# 08_PERIPHERAL.net
KiCad netlist of a schematic drawn in Altium Designer
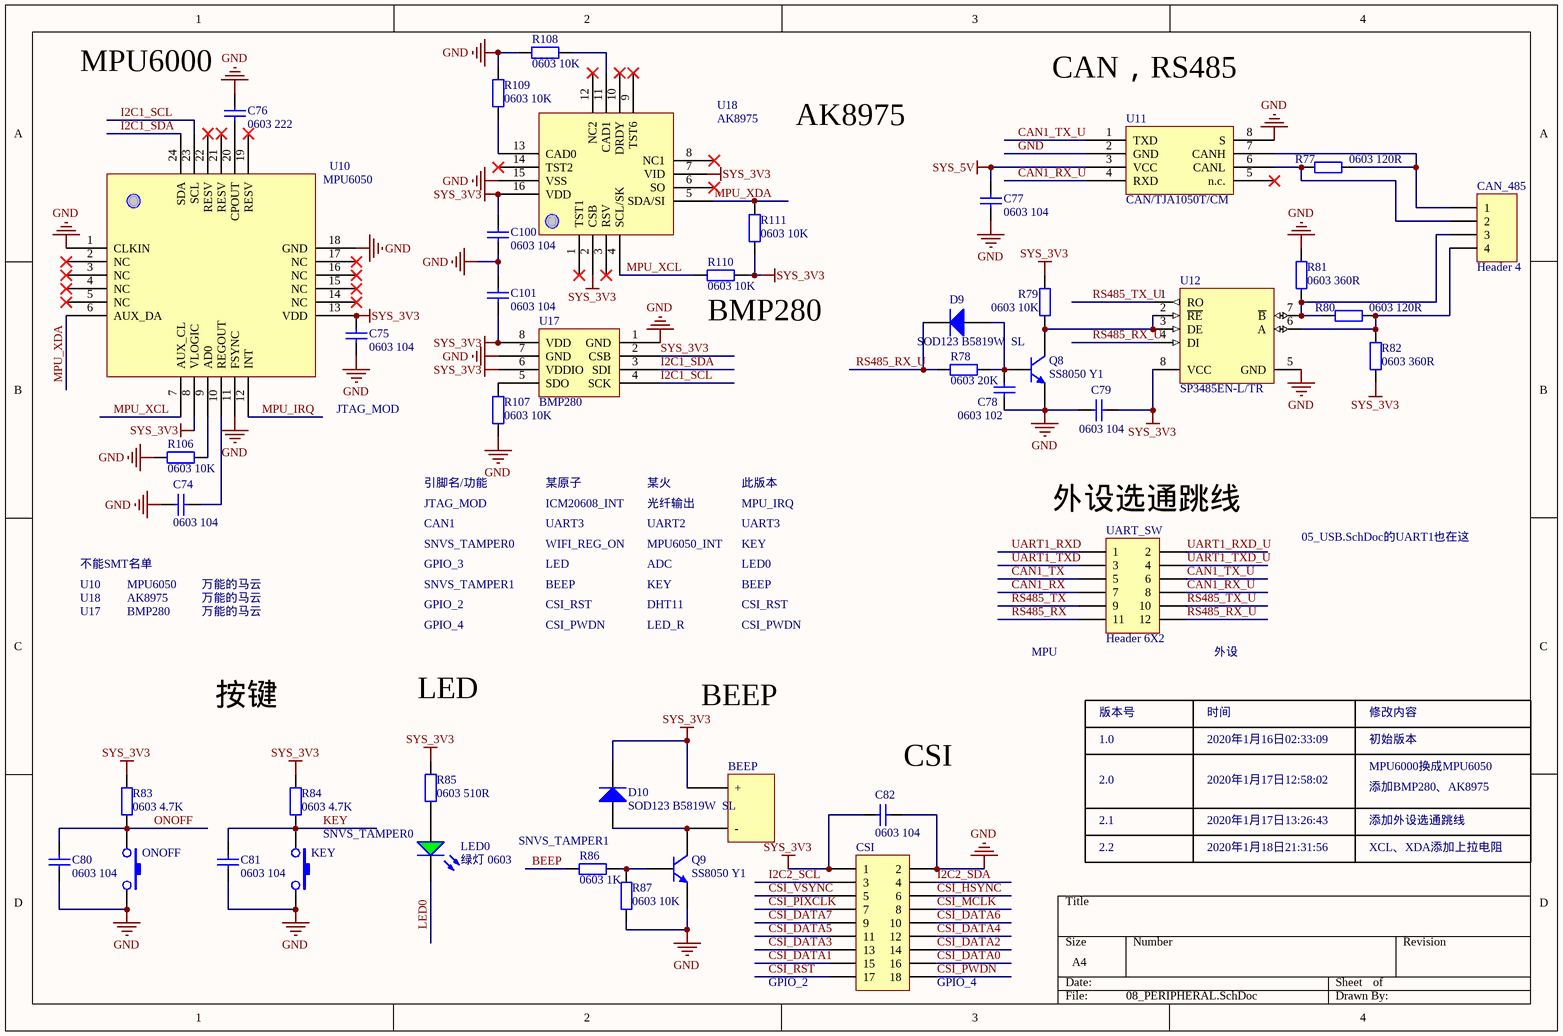
[diagram p0: 08_PERIPHERAL.SchDoc]

(export (version "E")
  (design (tool "Eeschema 10.0.6"))
  (components
    (comp (ref "BEEP") (value "~") (footprint "BEEP") (libsource (lib "Integrated_Library2") (part "BEEP")))
    (comp (ref "C74")
      (value "0603 104")
      (footprint "LC-0603_C")
      (description "贴片电容")
      (libsource (lib "JLC") (part "0603 1.5nF (152) 10% 50V"))
    )
    (comp (ref "C75")
      (value "0603 104")
      (footprint "LC-0603_C")
      (description "贴片电容")
      (libsource (lib "JLC") (part "0603 1.5nF (152) 10% 50V"))
    )
    (comp (ref "C76")
      (value "0603 222")
      (footprint "LC-0603_C")
      (description "贴片电容")
      (libsource (lib "JLC") (part "0603 1.5nF (152) 10% 50V"))
    )
    (comp (ref "C77")
      (value "0603 104")
      (footprint "LC-0603_C")
      (description "贴片电容")
      (libsource (lib "JLC") (part "0603 1.5nF (152) 10% 50V"))
    )
    (comp (ref "C78")
      (value "0603 102")
      (footprint "LC-0603_C")
      (description "贴片电容")
      (libsource (lib "JLC") (part "0603 1.5nF (152) 10% 50V"))
    )
    (comp (ref "C79")
      (value "0603 104")
      (footprint "LC-0603_C")
      (description "贴片电容")
      (libsource (lib "JLC") (part "0603 1.5nF (152) 10% 50V"))
    )
    (comp (ref "C80")
      (value "0603 104")
      (footprint "LC-0603_C")
      (description "贴片电容")
      (libsource (lib "JLC") (part "0603 1.5nF (152) 10% 50V"))
    )
    (comp (ref "C81")
      (value "0603 104")
      (footprint "LC-0603_C")
      (description "贴片电容")
      (libsource (lib "JLC") (part "0603 1.5nF (152) 10% 50V"))
    )
    (comp (ref "C82")
      (value "0603 104")
      (footprint "LC-0603_C")
      (description "贴片电容")
      (libsource (lib "JLC") (part "0603 1.5nF (152) 10% 50V"))
    )
    (comp (ref "C100")
      (value "0603 104")
      (footprint "LC-0603_C")
      (description "贴片电容")
      (libsource (lib "JLC") (part "0603 1.5nF (152) 10% 50V"))
    )
    (comp (ref "C101")
      (value "0603 104")
      (footprint "LC-0603_C")
      (description "贴片电容")
      (libsource (lib "JLC") (part "0603 1.5nF (152) 10% 50V"))
    )
    (comp (ref "CAN_485")
      (value "Header 4")
      (footprint "HDR1X4")
      (description "Header, 4-Pin")
      (fields (field (name "PUBLISHER") "Altium Limited"))
      (libsource (lib "Miscellaneous Connectors") (part "Header 4"))
    )
    (comp (ref "CSI")
      (value "~")
      (footprint "HDR2X9")
      (description "Header, 9-Pin, Dual row")
      (fields (field (name "PUBLISHER") "Altium Limited"))
      (libsource (lib "Miscellaneous Connectors") (part "Header 9X2"))
    )
    (comp (ref "D9")
      (value "SOD123 B5819W  SL")
      (footprint "LC-SOD-123")
      (description "肖特基二极管")
      (libsource (lib "JLC") (part "SOD-123 B5819W  SL"))
    )
    (comp (ref "D10")
      (value "SOD123 B5819W  SL")
      (footprint "LC-SOD-123")
      (description "肖特基二极管")
      (libsource (lib "JLC") (part "SOD-123 B5819W  SL"))
    )
    (comp (ref "KEY") (value "~") (footprint "KEY2") (libsource (lib "Integrated_Library2") (part "KEY")))
    (comp (ref "LED0")
      (value "绿灯 0603")
      (footprint "LC-0603_LED_S1")
      (description "发光二极管")
      (libsource (lib "JLC") (part "0603 绿灯"))
    )
    (comp (ref "ONOFF") (value "~") (footprint "KEY2") (libsource (lib "Integrated_Library2") (part "KEY")))
    (comp (ref "Q8")
      (value "SS8050 Y1")
      (footprint "LC-SOT-23(SOT-23-3)")
      (description "三极管")
      (libsource (lib "JLC") (part "SOT-23 SS8050 Y1"))
    )
    (comp (ref "Q9")
      (value "SS8050 Y1")
      (footprint "LC-SOT-23(SOT-23-3)")
      (description "三极管")
      (libsource (lib "JLC") (part "SOT-23 SS8050 Y1"))
    )
    (comp (ref "R77")
      (value "0603 120R")
      (footprint "LC-0603_R")
      (description "贴片电阻")
      (libsource (lib "") (part "0603 1.1KΩ (1101) 1%_1"))
    )
    (comp (ref "R78")
      (value "0603 20K")
      (footprint "LC-0603_R")
      (description "贴片电阻")
      (libsource (lib "") (part "0603 1.1KΩ (1101) 1%_2"))
    )
    (comp (ref "R79")
      (value "0603 10K")
      (footprint "LC-0603_R")
      (description "贴片电阻")
      (libsource (lib "JLC") (part "0603 1.1KΩ (1101) 1%"))
    )
    (comp (ref "R80")
      (value "0603 120R")
      (footprint "LC-0603_R")
      (description "贴片电阻")
      (libsource (lib "") (part "0603 1.1KΩ (1101) 1%_1"))
    )
    (comp (ref "R81")
      (value "0603 360R")
      (footprint "LC-0603_R")
      (description "贴片电阻")
      (libsource (lib "") (part "0603 1.1KΩ (1101) 1%_3"))
    )
    (comp (ref "R82")
      (value "0603 360R")
      (footprint "LC-0603_R")
      (description "贴片电阻")
      (libsource (lib "") (part "0603 1.1KΩ (1101) 1%_3"))
    )
    (comp (ref "R83")
      (value "0603 4.7K")
      (footprint "LC-0603_R")
      (description "贴片电阻")
      (libsource (lib "") (part "0603 1.1KΩ (1101) 1%_3"))
    )
    (comp (ref "R84")
      (value "0603 4.7K")
      (footprint "LC-0603_R")
      (description "贴片电阻")
      (libsource (lib "") (part "0603 1.1KΩ (1101) 1%_3"))
    )
    (comp (ref "R85")
      (value "0603 510R")
      (footprint "LC-0603_R")
      (description "贴片电阻")
      (libsource (lib "") (part "0603 1.1KΩ (1101) 1%_3"))
    )
    (comp (ref "R86")
      (value "0603 1K")
      (footprint "LC-0603_R")
      (description "贴片电阻")
      (libsource (lib "") (part "0603 1.1KΩ (1101) 1%_2"))
    )
    (comp (ref "R87")
      (value "0603 10K")
      (footprint "LC-0603_R")
      (description "贴片电阻")
      (libsource (lib "JLC") (part "0603 1.1KΩ (1101) 1%"))
    )
    (comp (ref "R106")
      (value "0603 10K")
      (footprint "LC-0603_R")
      (description "贴片电阻")
      (libsource (lib "") (part "0603 1.1KΩ (1101) 1%_1"))
    )
    (comp (ref "R107")
      (value "0603 10K")
      (footprint "LC-0603_R")
      (description "贴片电阻")
      (libsource (lib "") (part "0603 1.1KΩ (1101) 1%_3"))
    )
    (comp (ref "R108")
      (value "0603 10K")
      (footprint "LC-0603_R")
      (description "贴片电阻")
      (libsource (lib "") (part "0603 1.1KΩ (1101) 1%_2"))
    )
    (comp (ref "R109")
      (value "0603 10K")
      (footprint "LC-0603_R")
      (description "贴片电阻")
      (libsource (lib "JLC") (part "0603 1.1KΩ (1101) 1%"))
    )
    (comp (ref "R110")
      (value "0603 10K")
      (footprint "LC-0603_R")
      (description "贴片电阻")
      (libsource (lib "") (part "0603 1.1KΩ (1101) 1%_1"))
    )
    (comp (ref "R111")
      (value "0603 10K")
      (footprint "LC-0603_R")
      (description "贴片电阻")
      (libsource (lib "JLC") (part "0603 1.1KΩ (1101) 1%"))
    )
    (comp (ref "U10")
      (value "MPU6050")
      (footprint "QFN-24_4x4x05P")
      (libsource (lib "Integrated_Library2") (part "MPU6050"))
    )
    (comp (ref "U11")
      (value "CAN/TJA1050T/CM")
      (footprint "LC-SOIC-8_150mil")
      (description "CAN")
      (libsource (lib "JLC") (part "CAN/TJA1050T/CM"))
    )
    (comp (ref "U12")
      (value "SP3485EN-L/TR")
      (footprint "LC-SOIC-8_150mil")
      (description "RS-485/RS-422")
      (libsource (lib "JLC") (part "SP3485EN-L/TR"))
    )
    (comp (ref "U17")
      (value "BMP280")
      (footprint "BMP280")
      (libsource (lib "Integrated_Library2") (part "BMP280"))
    )
    (comp (ref "U18")
      (value "AK8975")
      (footprint "QFN16(4mm)")
      (libsource (lib "Integrated_Library2") (part "AK8975"))
    )
    (comp (ref "UART_SW")
      (value "Header 6X2")
      (footprint "HDR2X6")
      (description "Header, 6-Pin, Dual row")
      (fields (field (name "PUBLISHER") "Altium Limited"))
      (libsource (lib "Miscellaneous Connectors") (part "Header 6X2"))
    )
  )
  (nets
    (net (code "1") (name "/BEEP") (class "Default")
      (node (ref "R86") (pin "2") (pinfunction "2_2") (pintype "passive"))
    )
    (net (code "2") (name "/CAN1_RX") (class "Default")
      (node (ref "UART_SW") (pin "7") (pinfunction "7_7") (pintype "passive"))
    )
    (net (code "3") (name "/CAN1_RX_U") (class "Default")
      (node (ref "U11") (pin "4") (pinfunction "RXD_4") (pintype "passive"))
      (node (ref "UART_SW") (pin "8") (pinfunction "8_8") (pintype "passive"))
    )
    (net (code "4") (name "/CAN1_TX") (class "Default")
      (node (ref "UART_SW") (pin "5") (pinfunction "5_5") (pintype "passive"))
    )
    (net (code "5") (name "/CAN1_TX_U") (class "Default")
      (node (ref "U11") (pin "1") (pinfunction "TXD_1") (pintype "passive"))
      (node (ref "UART_SW") (pin "6") (pinfunction "6_6") (pintype "passive"))
    )
    (net (code "6") (name "/CSI_DATA0") (class "Default")
      (node (ref "CSI") (pin "16") (pinfunction "16_16") (pintype "passive"))
    )
    (net (code "7") (name "/CSI_DATA1") (class "Default")
      (node (ref "CSI") (pin "15") (pinfunction "15_15") (pintype "passive"))
    )
    (net (code "8") (name "/CSI_DATA2") (class "Default")
      (node (ref "CSI") (pin "14") (pinfunction "14_14") (pintype "passive"))
    )
    (net (code "9") (name "/CSI_DATA3") (class "Default")
      (node (ref "CSI") (pin "13") (pinfunction "13_13") (pintype "passive"))
    )
    (net (code "10") (name "/CSI_DATA4") (class "Default")
      (node (ref "CSI") (pin "12") (pinfunction "12_12") (pintype "passive"))
    )
    (net (code "11") (name "/CSI_DATA5") (class "Default")
      (node (ref "CSI") (pin "11") (pinfunction "11_11") (pintype "passive"))
    )
    (net (code "12") (name "/CSI_DATA6") (class "Default")
      (node (ref "CSI") (pin "10") (pinfunction "10_10") (pintype "passive"))
    )
    (net (code "13") (name "/CSI_DATA7") (class "Default")
      (node (ref "CSI") (pin "9") (pinfunction "9_9") (pintype "passive"))
    )
    (net (code "14") (name "/CSI_HSYNC") (class "Default")
      (node (ref "CSI") (pin "6") (pinfunction "6_6") (pintype "passive"))
    )
    (net (code "15") (name "/CSI_MCLK") (class "Default")
      (node (ref "CSI") (pin "8") (pinfunction "8_8") (pintype "passive"))
    )
    (net (code "16") (name "/CSI_PIXCLK") (class "Default")
      (node (ref "CSI") (pin "7") (pinfunction "7_7") (pintype "passive"))
    )
    (net (code "17") (name "/CSI_PWDN") (class "Default")
      (node (ref "CSI") (pin "18") (pinfunction "18_18") (pintype "passive"))
    )
    (net (code "18") (name "/CSI_RST") (class "Default")
      (node (ref "CSI") (pin "17") (pinfunction "17_17") (pintype "passive"))
    )
    (net (code "19") (name "/CSI_VSYNC") (class "Default")
      (node (ref "CSI") (pin "5") (pinfunction "5_5") (pintype "passive"))
    )
    (net (code "20") (name "/I2C1_SCL") (class "Default")
      (node (ref "U10") (pin "23") (pinfunction "SCL_23") (pintype "passive"))
      (node (ref "U17") (pin "4") (pinfunction "SCK_4") (pintype "passive"))
    )
    (net (code "21") (name "/I2C1_SDA") (class "Default")
      (node (ref "U10") (pin "24") (pinfunction "SDA_24") (pintype "passive"))
      (node (ref "U17") (pin "3") (pinfunction "SDI_3") (pintype "passive"))
    )
    (net (code "22") (name "/I2C2_SCL") (class "Default")
      (node (ref "CSI") (pin "3") (pinfunction "3_3") (pintype "passive"))
    )
    (net (code "23") (name "/I2C2_SDA") (class "Default")
      (node (ref "CSI") (pin "4") (pinfunction "4_4") (pintype "passive"))
    )
    (net (code "24") (name "/KEY") (class "Default")
      (node (ref "C81") (pin "2") (pinfunction "2_2") (pintype "passive"))
      (node (ref "KEY") (pin "1") (pinfunction "1_1") (pintype "passive"))
      (node (ref "R84") (pin "1") (pinfunction "1_1") (pintype "passive"))
    )
    (net (code "25") (name "/LED0") (class "Default")
      (node (ref "LED0") (pin "K") (pinfunction "K_K") (pintype "passive"))
    )
    (net (code "26") (name "/MPU_IRQ") (class "Default")
      (node (ref "U10") (pin "12") (pinfunction "INT_12") (pintype "passive"))
    )
    (net (code "27") (name "/MPU_XCL") (class "Default")
      (node (ref "R110") (pin "1") (pinfunction "1_1") (pintype "passive"))
      (node (ref "U10") (pin "7") (pinfunction "AUX_CL_7") (pintype "passive"))
      (node (ref "U18") (pin "4") (pinfunction "SCL/SK_4") (pintype "passive"))
    )
    (net (code "28") (name "/MPU_XDA") (class "Default")
      (node (ref "R111") (pin "1") (pinfunction "1_1") (pintype "passive"))
      (node (ref "U10") (pin "6") (pinfunction "AUX_DA_6") (pintype "passive"))
      (node (ref "U18") (pin "5") (pinfunction "SDA/SI_5") (pintype "passive"))
    )
    (net (code "29") (name "/ONOFF") (class "Default")
      (node (ref "C80") (pin "2") (pinfunction "2_2") (pintype "passive"))
      (node (ref "ONOFF") (pin "1") (pinfunction "1_1") (pintype "passive"))
      (node (ref "R83") (pin "1") (pinfunction "1_1") (pintype "passive"))
    )
    (net (code "30") (name "/RS485_RX") (class "Default")
      (node (ref "UART_SW") (pin "11") (pinfunction "11_11") (pintype "passive"))
    )
    (net (code "31") (name "/RS485_RX_U") (class "Default")
      (node (ref "D9") (pin "2") (pinfunction "K_2") (pintype "passive"))
      (node (ref "R78") (pin "2") (pinfunction "2_2") (pintype "passive"))
      (node (ref "U12") (pin "4") (pinfunction "DI_4") (pintype "input"))
      (node (ref "UART_SW") (pin "12") (pinfunction "12_12") (pintype "passive"))
    )
    (net (code "32") (name "/RS485_TX") (class "Default")
      (node (ref "UART_SW") (pin "9") (pinfunction "9_9") (pintype "passive"))
    )
    (net (code "33") (name "/RS485_TX_U") (class "Default")
      (node (ref "U12") (pin "1") (pinfunction "RO_1") (pintype "output"))
      (node (ref "UART_SW") (pin "10") (pinfunction "10_10") (pintype "passive"))
    )
    (net (code "34") (name "/UART1_RXD") (class "Default")
      (node (ref "UART_SW") (pin "1") (pinfunction "1_1") (pintype "passive"))
    )
    (net (code "35") (name "/UART1_RXD_U") (class "Default")
      (node (ref "UART_SW") (pin "2") (pinfunction "2_2") (pintype "passive"))
    )
    (net (code "36") (name "/UART1_TXD") (class "Default")
      (node (ref "UART_SW") (pin "3") (pinfunction "3_3") (pintype "passive"))
    )
    (net (code "37") (name "/UART1_TXD_U") (class "Default")
      (node (ref "UART_SW") (pin "4") (pinfunction "4_4") (pintype "passive"))
    )
    (net (code "38") (name "GND") (class "Default")
      (node (ref "C100") (pin "2") (pinfunction "2_2") (pintype "passive"))
      (node (ref "C101") (pin "1") (pinfunction "1_1") (pintype "passive"))
      (node (ref "C74") (pin "1") (pinfunction "1_1") (pintype "passive"))
      (node (ref "C75") (pin "1") (pinfunction "1_1") (pintype "passive"))
      (node (ref "C76") (pin "2") (pinfunction "2_2") (pintype "passive"))
      (node (ref "C77") (pin "1") (pinfunction "1_1") (pintype "passive"))
      (node (ref "C78") (pin "2") (pinfunction "2_2") (pintype "passive"))
      (node (ref "C79") (pin "1") (pinfunction "1_1") (pintype "passive"))
      (node (ref "C80") (pin "1") (pinfunction "1_1") (pintype "passive"))
      (node (ref "C81") (pin "1") (pinfunction "1_1") (pintype "passive"))
      (node (ref "C82") (pin "1") (pinfunction "1_1") (pintype "passive"))
      (node (ref "CSI") (pin "2") (pinfunction "2_2") (pintype "passive"))
      (node (ref "KEY") (pin "2") (pinfunction "2_2") (pintype "passive"))
      (node (ref "ONOFF") (pin "2") (pinfunction "2_2") (pintype "passive"))
      (node (ref "Q8") (pin "2") (pinfunction "E_2") (pintype "passive"))
      (node (ref "Q9") (pin "2") (pinfunction "E_2") (pintype "passive"))
      (node (ref "R106") (pin "1") (pinfunction "1_1") (pintype "passive"))
      (node (ref "R107") (pin "1") (pinfunction "1_1") (pintype "passive"))
      (node (ref "R108") (pin "2") (pinfunction "2_2") (pintype "passive"))
      (node (ref "R109") (pin "1") (pinfunction "1_1") (pintype "passive"))
      (node (ref "R81") (pin "2") (pinfunction "2_2") (pintype "passive"))
      (node (ref "R87") (pin "2") (pinfunction "2_2") (pintype "passive"))
      (node (ref "U10") (pin "1") (pinfunction "CLKIN_1") (pintype "passive"))
      (node (ref "U10") (pin "11") (pinfunction "FSYNC_11") (pintype "passive"))
      (node (ref "U10") (pin "18") (pinfunction "GND_18") (pintype "passive"))
      (node (ref "U11") (pin "2") (pinfunction "GND_2") (pintype "passive"))
      (node (ref "U11") (pin "8") (pinfunction "S_8") (pintype "passive"))
      (node (ref "U12") (pin "5") (pinfunction "GND_5") (pintype "power_in"))
      (node (ref "U17") (pin "1") (pinfunction "GND_1") (pintype "passive"))
      (node (ref "U17") (pin "7") (pinfunction "GND_7") (pintype "passive"))
      (node (ref "U18") (pin "15") (pinfunction "VSS_15") (pintype "passive"))
    )
    (net (code "39") (name "Net-(D9-A)") (class "Default")
      (node (ref "C78") (pin "1") (pinfunction "1_1") (pintype "passive"))
      (node (ref "D9") (pin "1") (pinfunction "A_1") (pintype "passive"))
      (node (ref "Q8") (pin "1") (pinfunction "B_1") (pintype "passive"))
      (node (ref "R78") (pin "1") (pinfunction "1_1") (pintype "passive"))
    )
    (net (code "40") (name "Net-(D10-A)") (class "Default")
      (node (ref "BEEP") (pin "-") (pinfunction "-_-") (pintype "passive"))
      (node (ref "D10") (pin "1") (pinfunction "A_1") (pintype "passive"))
      (node (ref "Q9") (pin "3") (pinfunction "C_3") (pintype "passive"))
    )
    (net (code "41") (name "Net-(LED0-PadA)") (class "Default")
      (node (ref "LED0") (pin "A") (pinfunction "A_A") (pintype "passive"))
      (node (ref "R85") (pin "1") (pinfunction "1_1") (pintype "passive"))
    )
    (net (code "42") (name "Net-(Q8-C)") (class "Default")
      (node (ref "Q8") (pin "3") (pinfunction "C_3") (pintype "passive"))
      (node (ref "R79") (pin "2") (pinfunction "2_2") (pintype "passive"))
      (node (ref "U12") (pin "2") (pinfunction "~{RE}_2") (pintype "input"))
      (node (ref "U12") (pin "3") (pinfunction "DE_3") (pintype "input"))
    )
    (net (code "43") (name "Net-(Q9-B)") (class "Default")
      (node (ref "Q9") (pin "1") (pinfunction "B_1") (pintype "passive"))
      (node (ref "R86") (pin "1") (pinfunction "1_1") (pintype "passive"))
      (node (ref "R87") (pin "1") (pinfunction "1_1") (pintype "passive"))
    )
    (net (code "44") (name "Net-(U10-AD0)") (class "Default")
      (node (ref "R106") (pin "2") (pinfunction "2_2") (pintype "passive"))
      (node (ref "U10") (pin "9") (pinfunction "AD0_9") (pintype "passive"))
    )
    (net (code "45") (name "Net-(U10-CPOUT)") (class "Default")
      (node (ref "C76") (pin "1") (pinfunction "1_1") (pintype "passive"))
      (node (ref "U10") (pin "20") (pinfunction "CPOUT_20") (pintype "passive"))
    )
    (net (code "46") (name "Net-(U10-REGOUT)") (class "Default")
      (node (ref "C74") (pin "2") (pinfunction "2_2") (pintype "passive"))
      (node (ref "U10") (pin "10") (pinfunction "REGOUT_10") (pintype "passive"))
    )
    (net (code "47") (name "Net-(U11-CANH)") (class "Default")
      (node (ref "CAN_485") (pin "1") (pinfunction "1_1") (pintype "passive"))
      (node (ref "R77") (pin "2") (pinfunction "2_2") (pintype "passive"))
      (node (ref "U11") (pin "7") (pinfunction "CANH_7") (pintype "passive"))
    )
    (net (code "48") (name "Net-(U11-CANL)") (class "Default")
      (node (ref "CAN_485") (pin "2") (pinfunction "2_2") (pintype "passive"))
      (node (ref "R77") (pin "1") (pinfunction "1_1") (pintype "passive"))
      (node (ref "U11") (pin "6") (pinfunction "CANL_6") (pintype "passive"))
    )
    (net (code "49") (name "Net-(U12-A)") (class "Default")
      (node (ref "CAN_485") (pin "4") (pinfunction "4_4") (pintype "passive"))
      (node (ref "R80") (pin "2") (pinfunction "2_2") (pintype "passive"))
      (node (ref "R82") (pin "2") (pinfunction "2_2") (pintype "passive"))
      (node (ref "U12") (pin "6") (pinfunction "A_6") (pintype "bidirectional"))
    )
    (net (code "50") (name "Net-(U12-~{B})") (class "Default")
      (node (ref "CAN_485") (pin "3") (pinfunction "3_3") (pintype "passive"))
      (node (ref "R80") (pin "1") (pinfunction "1_1") (pintype "passive"))
      (node (ref "R81") (pin "1") (pinfunction "1_1") (pintype "passive"))
      (node (ref "U12") (pin "7") (pinfunction "~{B}_7") (pintype "bidirectional"))
    )
    (net (code "51") (name "Net-(U17-SDO)") (class "Default")
      (node (ref "R107") (pin "2") (pinfunction "2_2") (pintype "passive"))
      (node (ref "U17") (pin "5") (pinfunction "SDO_5") (pintype "passive"))
    )
    (net (code "52") (name "Net-(U18-CAD0)") (class "Default")
      (node (ref "R109") (pin "2") (pinfunction "2_2") (pintype "passive"))
      (node (ref "U18") (pin "13") (pinfunction "CAD0_13") (pintype "passive"))
    )
    (net (code "53") (name "Net-(U18-CAD1)") (class "Default")
      (node (ref "R108") (pin "1") (pinfunction "1_1") (pintype "passive"))
      (node (ref "U18") (pin "11") (pinfunction "CAD1_11") (pintype "passive"))
    )
    (net (code "54") (name "SYS_3V3") (class "Default")
      (node (ref "BEEP") (pin "+") (pinfunction "+_+") (pintype "passive"))
      (node (ref "C100") (pin "1") (pinfunction "1_1") (pintype "passive"))
      (node (ref "C101") (pin "2") (pinfunction "2_2") (pintype "passive"))
      (node (ref "C75") (pin "2") (pinfunction "2_2") (pintype "passive"))
      (node (ref "C79") (pin "2") (pinfunction "2_2") (pintype "passive"))
      (node (ref "C82") (pin "2") (pinfunction "2_2") (pintype "passive"))
      (node (ref "CSI") (pin "1") (pinfunction "1_1") (pintype "passive"))
      (node (ref "D10") (pin "2") (pinfunction "K_2") (pintype "passive"))
      (node (ref "R110") (pin "2") (pinfunction "2_2") (pintype "passive"))
      (node (ref "R111") (pin "2") (pinfunction "2_2") (pintype "passive"))
      (node (ref "R79") (pin "1") (pinfunction "1_1") (pintype "passive"))
      (node (ref "R82") (pin "1") (pinfunction "1_1") (pintype "passive"))
      (node (ref "R83") (pin "2") (pinfunction "2_2") (pintype "passive"))
      (node (ref "R84") (pin "2") (pinfunction "2_2") (pintype "passive"))
      (node (ref "R85") (pin "2") (pinfunction "2_2") (pintype "passive"))
      (node (ref "U10") (pin "13") (pinfunction "VDD_13") (pintype "passive"))
      (node (ref "U10") (pin "8") (pinfunction "VLOGIC_8") (pintype "passive"))
      (node (ref "U12") (pin "8") (pinfunction "VCC_8") (pintype "power_in"))
      (node (ref "U17") (pin "2") (pinfunction "CSB_2") (pintype "passive"))
      (node (ref "U17") (pin "6") (pinfunction "VDDIO_6") (pintype "passive"))
      (node (ref "U17") (pin "8") (pinfunction "VDD_8") (pintype "passive"))
      (node (ref "U18") (pin "16") (pinfunction "VDD_16") (pintype "passive"))
      (node (ref "U18") (pin "2") (pinfunction "CSB_2") (pintype "passive"))
    )
    (net (code "55") (name "SYS_5V") (class "Default")
      (node (ref "C77") (pin "2") (pinfunction "2_2") (pintype "passive"))
      (node (ref "U11") (pin "3") (pinfunction "VCC_3") (pintype "passive"))
    )
    (net (code "56") (name "unconnected-(U10-NC-Pad2)") (class "Default")
      (node (ref "U10") (pin "2") (pinfunction "NC_2") (pintype "passive+no_connect"))
    )
    (net (code "57") (name "unconnected-(U10-NC-Pad3)") (class "Default")
      (node (ref "U10") (pin "3") (pinfunction "NC_3") (pintype "passive+no_connect"))
    )
    (net (code "58") (name "unconnected-(U10-NC-Pad4)") (class "Default")
      (node (ref "U10") (pin "4") (pinfunction "NC_4") (pintype "passive+no_connect"))
    )
    (net (code "59") (name "unconnected-(U10-NC-Pad5)") (class "Default")
      (node (ref "U10") (pin "5") (pinfunction "NC_5") (pintype "passive+no_connect"))
    )
    (net (code "60") (name "unconnected-(U10-NC-Pad14)") (class "Default")
      (node (ref "U10") (pin "14") (pinfunction "NC_14") (pintype "passive+no_connect"))
    )
    (net (code "61") (name "unconnected-(U10-NC-Pad15)") (class "Default")
      (node (ref "U10") (pin "15") (pinfunction "NC_15") (pintype "passive+no_connect"))
    )
    (net (code "62") (name "unconnected-(U10-NC-Pad16)") (class "Default")
      (node (ref "U10") (pin "16") (pinfunction "NC_16") (pintype "passive+no_connect"))
    )
    (net (code "63") (name "unconnected-(U10-NC-Pad17)") (class "Default")
      (node (ref "U10") (pin "17") (pinfunction "NC_17") (pintype "passive+no_connect"))
    )
    (net (code "64") (name "unconnected-(U10-RESV-Pad19)") (class "Default")
      (node (ref "U10") (pin "19") (pinfunction "RESV_19") (pintype "passive+no_connect"))
    )
    (net (code "65") (name "unconnected-(U10-RESV-Pad21)") (class "Default")
      (node (ref "U10") (pin "21") (pinfunction "RESV_21") (pintype "passive+no_connect"))
    )
    (net (code "66") (name "unconnected-(U10-RESV-Pad22)") (class "Default")
      (node (ref "U10") (pin "22") (pinfunction "RESV_22") (pintype "passive+no_connect"))
    )
    (net (code "67") (name "unconnected-(U11-n.c.-Pad5)") (class "Default")
      (node (ref "U11") (pin "5") (pinfunction "n.c._5") (pintype "passive+no_connect"))
    )
    (net (code "68") (name "unconnected-(U18-DRDY-Pad10)") (class "Default")
      (node (ref "U18") (pin "10") (pinfunction "DRDY_10") (pintype "passive+no_connect"))
    )
    (net (code "69") (name "unconnected-(U18-NC1-Pad8)") (class "Default")
      (node (ref "U18") (pin "8") (pinfunction "NC1_8") (pintype "passive+no_connect"))
    )
    (net (code "70") (name "unconnected-(U18-NC2-Pad12)") (class "Default")
      (node (ref "U18") (pin "12") (pinfunction "NC2_12") (pintype "passive+no_connect"))
    )
    (net (code "71") (name "unconnected-(U18-RSV-Pad3)") (class "Default")
      (node (ref "U18") (pin "3") (pinfunction "RSV_3") (pintype "passive+no_connect"))
    )
    (net (code "72") (name "unconnected-(U18-SO-Pad6)") (class "Default")
      (node (ref "U18") (pin "6") (pinfunction "SO_6") (pintype "passive+no_connect"))
    )
    (net (code "73") (name "unconnected-(U18-TST1-Pad1)") (class "Default")
      (node (ref "U18") (pin "1") (pinfunction "TST1_1") (pintype "passive+no_connect"))
    )
    (net (code "74") (name "unconnected-(U18-TST2-Pad14)") (class "Default")
      (node (ref "U18") (pin "14") (pinfunction "TST2_14") (pintype "passive+no_connect"))
    )
    (net (code "75") (name "unconnected-(U18-TST6-Pad9)") (class "Default")
      (node (ref "U18") (pin "9") (pinfunction "TST6_9") (pintype "passive+no_connect"))
    )
    (net (code "76") (name "unconnected-(U18-VID-Pad7)") (class "Default")
      (node (ref "U18") (pin "7") (pinfunction "VID_7") (pintype "passive"))
    )
  )
)
